# Sheet2.net
KiCad netlist of a schematic drawn in Altium Designer
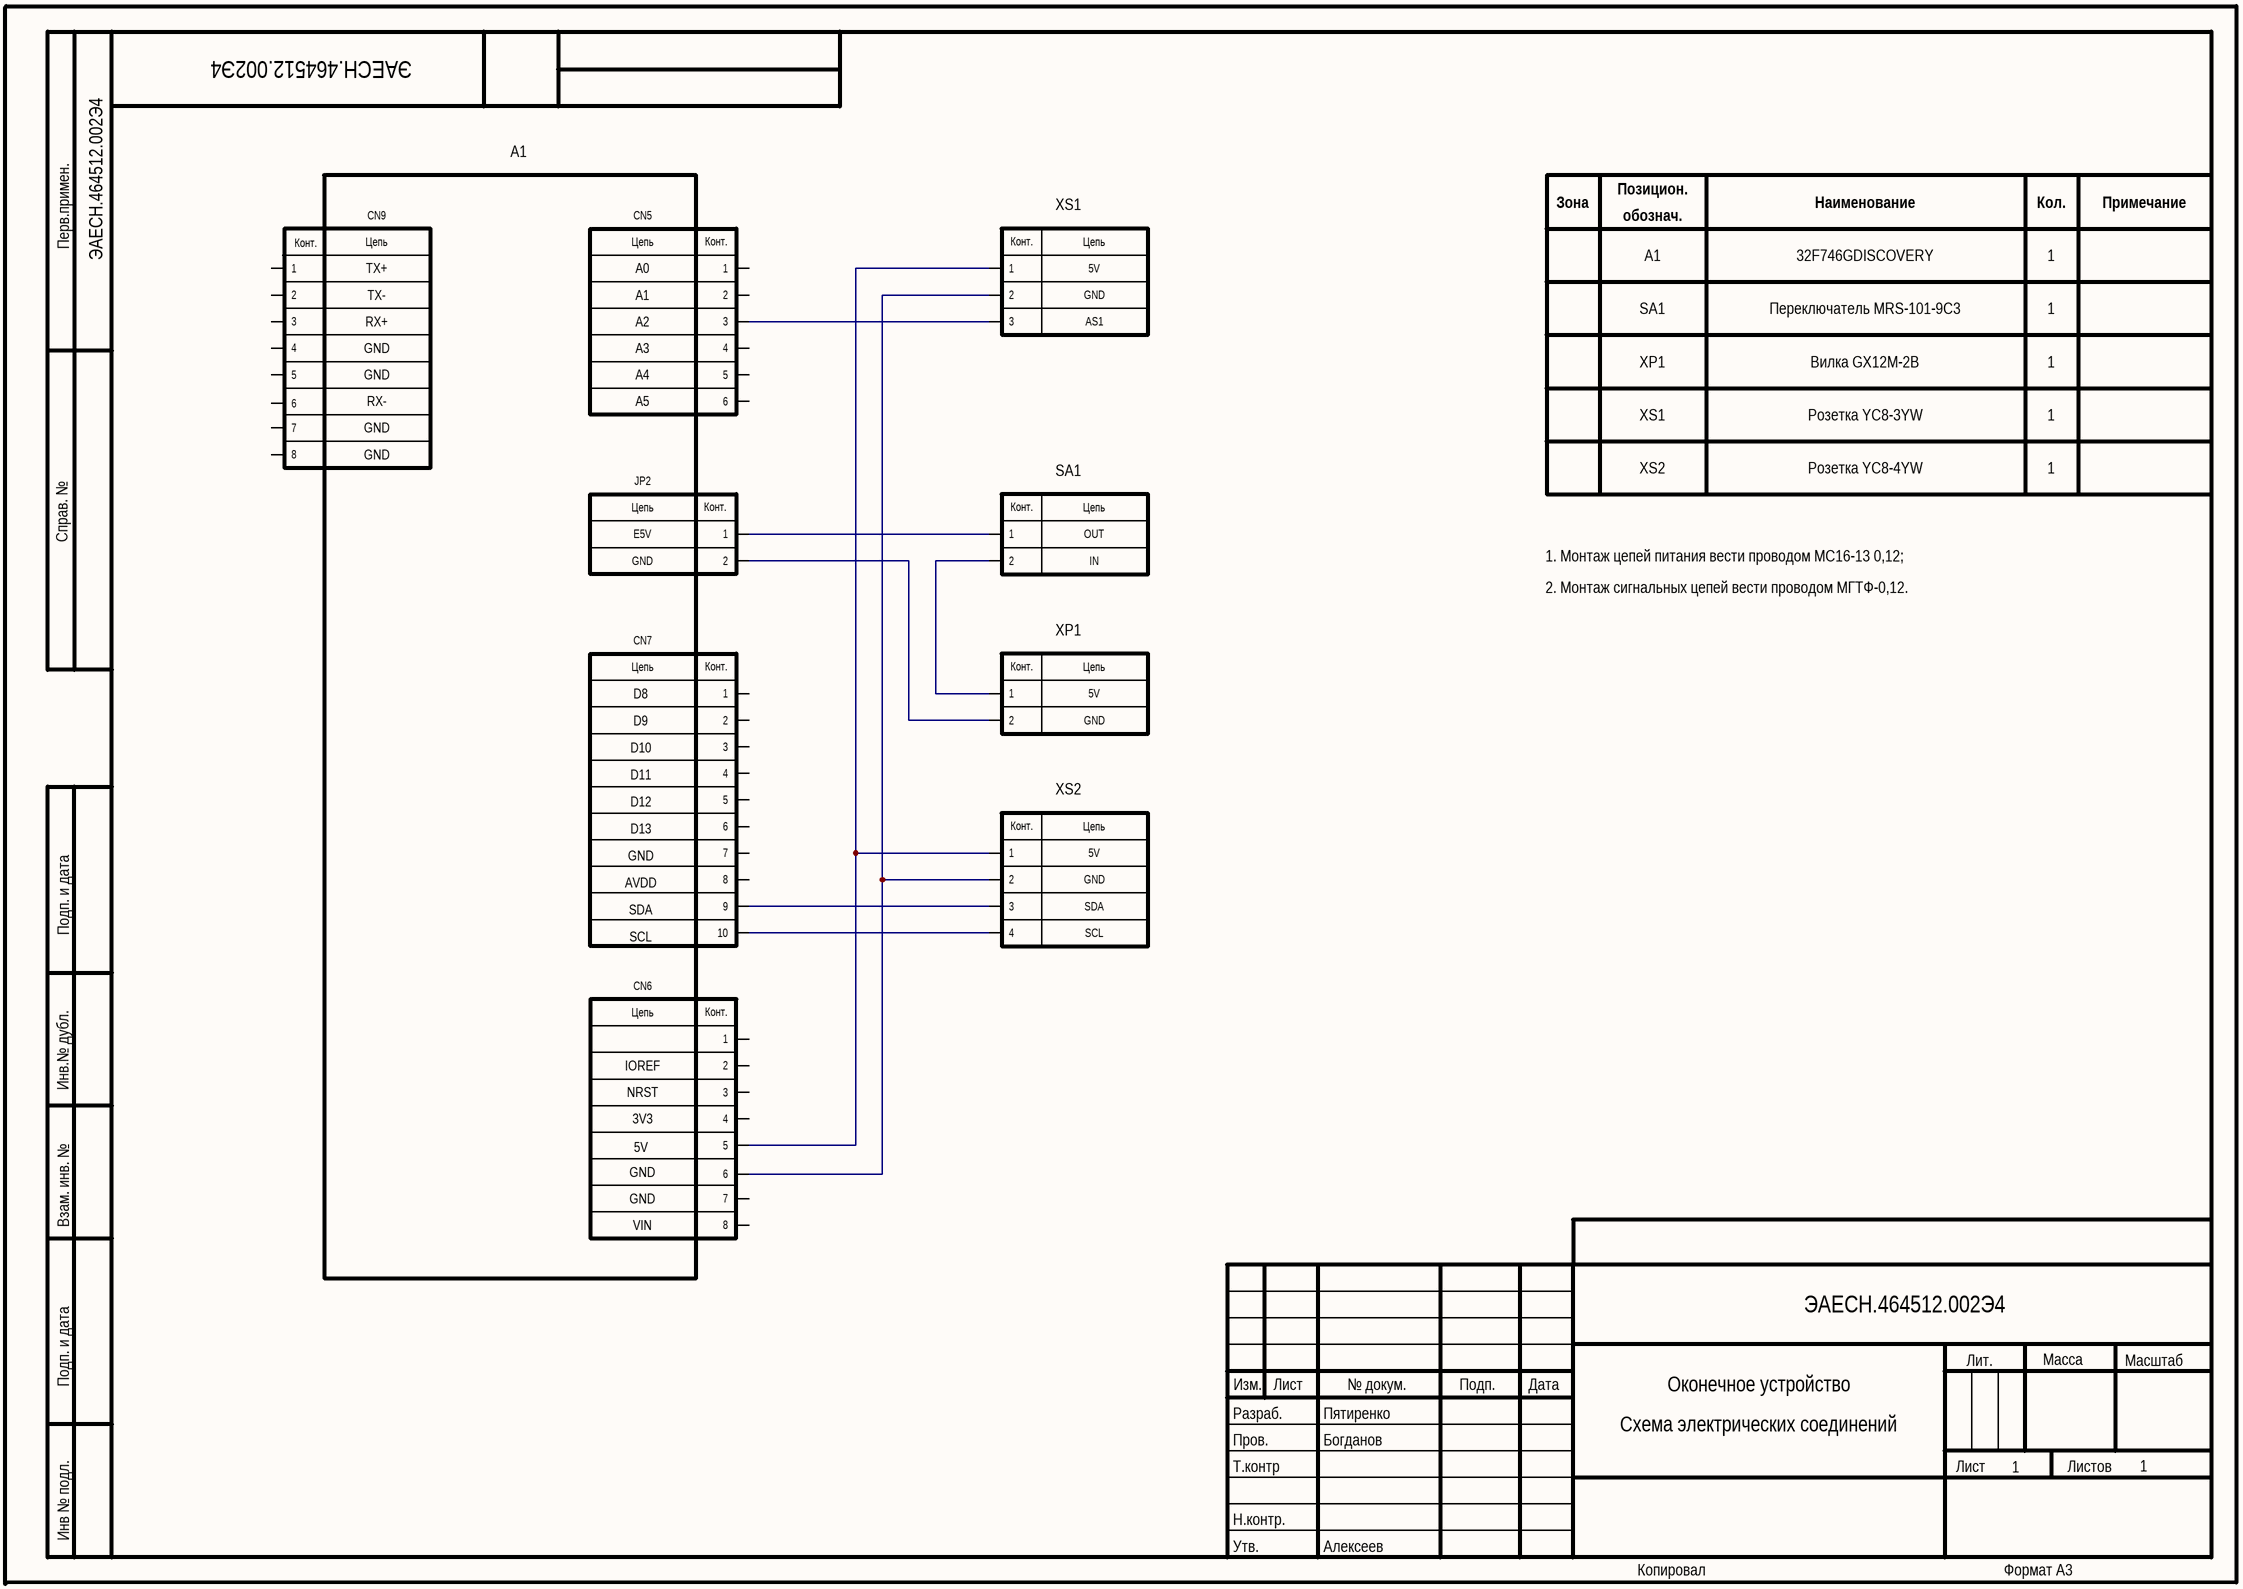
[diagram p0: Sheet2.SchDoc]

(export (version "E")
  (design (tool "Eeschema 10.0.6"))
  (components
    (comp (ref "A1") (value "32F746GDISCOVERY") (libsource (lib "Schlib1") (part "32F746GDISCOVERY")))
    (comp (ref "SA1") (value "MRS-101-9C3") (libsource (lib "Schlib1") (part "MRS-101-9C3")))
    (comp (ref "XP1") (value "GX12M-2B") (libsource (lib "Schlib1") (part "GX12M-2B")))
    (comp (ref "XS1") (value "YC8-3YW") (libsource (lib "Schlib1") (part "YC8-3YW")))
    (comp (ref "XS2") (value "YC8-4YW") (libsource (lib "Schlib1") (part "YC8-4YW")))
  )
  (nets
    (net (code "1") (name "Net-(A1-Pad1)_3") (class "Default")
      (node (ref "A1") (pin "1") (pinfunction "1_1") (pintype "passive"))
      (node (ref "SA1") (pin "1") (pinfunction "1_1") (pintype "passive"))
    )
    (net (code "2") (name "Net-(A1-Pad2)_3") (class "Default")
      (node (ref "A1") (pin "2") (pinfunction "2_2") (pintype "passive"))
      (node (ref "XP1") (pin "2") (pinfunction "2_2") (pintype "passive"))
    )
    (net (code "3") (name "Net-(A1-Pad3)_2") (class "Default")
      (node (ref "A1") (pin "3") (pinfunction "3_3") (pintype "passive"))
      (node (ref "XS1") (pin "3") (pinfunction "3_3") (pintype "passive"))
    )
    (net (code "4") (name "Net-(A1-Pad5)_1") (class "Default")
      (node (ref "A1") (pin "5") (pinfunction "5_5") (pintype "passive"))
      (node (ref "XS1") (pin "1") (pinfunction "1_1") (pintype "passive"))
      (node (ref "XS2") (pin "1") (pinfunction "1_1") (pintype "passive"))
    )
    (net (code "5") (name "Net-(A1-Pad6)_1") (class "Default")
      (node (ref "A1") (pin "6") (pinfunction "6_6") (pintype "passive"))
      (node (ref "XS1") (pin "2") (pinfunction "2_2") (pintype "passive"))
      (node (ref "XS2") (pin "2") (pinfunction "2_2") (pintype "passive"))
    )
    (net (code "6") (name "Net-(A1-Pad9)") (class "Default")
      (node (ref "A1") (pin "9") (pinfunction "9_9") (pintype "passive"))
      (node (ref "XS2") (pin "3") (pinfunction "3_3") (pintype "passive"))
    )
    (net (code "7") (name "Net-(A1-Pad10)") (class "Default")
      (node (ref "A1") (pin "10") (pinfunction "10_10") (pintype "passive"))
      (node (ref "XS2") (pin "4") (pinfunction "4_4") (pintype "passive"))
    )
    (net (code "8") (name "Net-(SA1-Pad2)") (class "Default")
      (node (ref "SA1") (pin "2") (pinfunction "2_2") (pintype "passive"))
      (node (ref "XP1") (pin "1") (pinfunction "1_1") (pintype "passive"))
    )
    (net (code "9") (name "unconnected-(A1-Pad1)") (class "Default")
      (node (ref "A1") (pin "1") (pinfunction "1_1") (pintype "passive"))
    )
    (net (code "10") (name "unconnected-(A1-Pad1)_1") (class "Default")
      (node (ref "A1") (pin "1") (pinfunction "1_1") (pintype "passive"))
    )
    (net (code "11") (name "unconnected-(A1-Pad1)_2") (class "Default")
      (node (ref "A1") (pin "1") (pinfunction "1_1") (pintype "passive"))
    )
    (net (code "12") (name "unconnected-(A1-Pad1)_4") (class "Default")
      (node (ref "A1") (pin "1") (pinfunction "1_1") (pintype "passive"))
    )
    (net (code "13") (name "unconnected-(A1-Pad2)") (class "Default")
      (node (ref "A1") (pin "2") (pinfunction "2_2") (pintype "passive"))
    )
    (net (code "14") (name "unconnected-(A1-Pad2)_1") (class "Default")
      (node (ref "A1") (pin "2") (pinfunction "2_2") (pintype "passive"))
    )
    (net (code "15") (name "unconnected-(A1-Pad2)_2") (class "Default")
      (node (ref "A1") (pin "2") (pinfunction "2_2") (pintype "passive"))
    )
    (net (code "16") (name "unconnected-(A1-Pad2)_4") (class "Default")
      (node (ref "A1") (pin "2") (pinfunction "2_2") (pintype "passive"))
    )
    (net (code "17") (name "unconnected-(A1-Pad3)") (class "Default")
      (node (ref "A1") (pin "3") (pinfunction "3_3") (pintype "passive"))
    )
    (net (code "18") (name "unconnected-(A1-Pad3)_1") (class "Default")
      (node (ref "A1") (pin "3") (pinfunction "3_3") (pintype "passive"))
    )
    (net (code "19") (name "unconnected-(A1-Pad3)_3") (class "Default")
      (node (ref "A1") (pin "3") (pinfunction "3_3") (pintype "passive"))
    )
    (net (code "20") (name "unconnected-(A1-Pad4)") (class "Default")
      (node (ref "A1") (pin "4") (pinfunction "4_4") (pintype "passive"))
    )
    (net (code "21") (name "unconnected-(A1-Pad4)_1") (class "Default")
      (node (ref "A1") (pin "4") (pinfunction "4_4") (pintype "passive"))
    )
    (net (code "22") (name "unconnected-(A1-Pad4)_2") (class "Default")
      (node (ref "A1") (pin "4") (pinfunction "4_4") (pintype "passive"))
    )
    (net (code "23") (name "unconnected-(A1-Pad4)_3") (class "Default")
      (node (ref "A1") (pin "4") (pinfunction "4_4") (pintype "passive"))
    )
    (net (code "24") (name "unconnected-(A1-Pad5)") (class "Default")
      (node (ref "A1") (pin "5") (pinfunction "5_5") (pintype "passive"))
    )
    (net (code "25") (name "unconnected-(A1-Pad5)_2") (class "Default")
      (node (ref "A1") (pin "5") (pinfunction "5_5") (pintype "passive"))
    )
    (net (code "26") (name "unconnected-(A1-Pad5)_3") (class "Default")
      (node (ref "A1") (pin "5") (pinfunction "5_5") (pintype "passive"))
    )
    (net (code "27") (name "unconnected-(A1-Pad6)") (class "Default")
      (node (ref "A1") (pin "6") (pinfunction "6_6") (pintype "passive"))
    )
    (net (code "28") (name "unconnected-(A1-Pad6)_2") (class "Default")
      (node (ref "A1") (pin "6") (pinfunction "6_6") (pintype "passive"))
    )
    (net (code "29") (name "unconnected-(A1-Pad6)_3") (class "Default")
      (node (ref "A1") (pin "6") (pinfunction "6_6") (pintype "passive"))
    )
    (net (code "30") (name "unconnected-(A1-Pad7)") (class "Default")
      (node (ref "A1") (pin "7") (pinfunction "7_7") (pintype "passive"))
    )
    (net (code "31") (name "unconnected-(A1-Pad7)_1") (class "Default")
      (node (ref "A1") (pin "7") (pinfunction "7_7") (pintype "passive"))
    )
    (net (code "32") (name "unconnected-(A1-Pad7)_2") (class "Default")
      (node (ref "A1") (pin "7") (pinfunction "7_7") (pintype "passive"))
    )
    (net (code "33") (name "unconnected-(A1-Pad8)") (class "Default")
      (node (ref "A1") (pin "8") (pinfunction "8_8") (pintype "passive"))
    )
    (net (code "34") (name "unconnected-(A1-Pad8)_1") (class "Default")
      (node (ref "A1") (pin "8") (pinfunction "8_8") (pintype "passive"))
    )
    (net (code "35") (name "unconnected-(A1-Pad8)_2") (class "Default")
      (node (ref "A1") (pin "8") (pinfunction "8_8") (pintype "passive"))
    )
  )
)
